# Motor_Control_-_Phase_A.net
KiCad netlist of a schematic drawn in Altium Designer
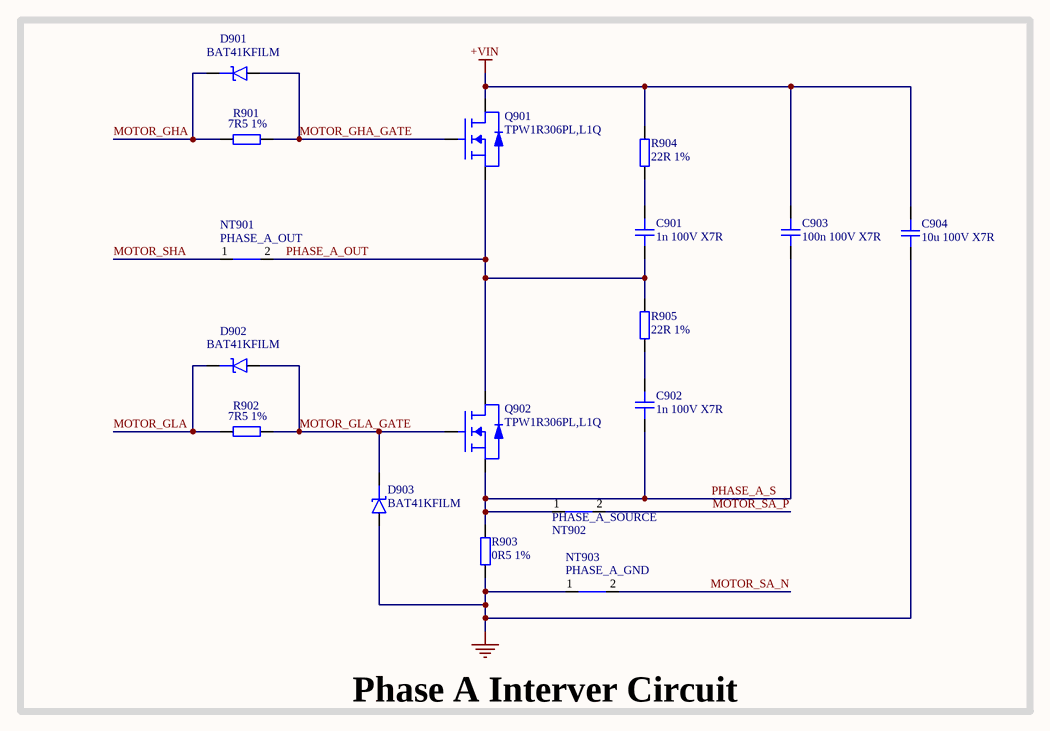
[diagram p0: Motor Control - Phase A.SchDoc]

(export (version "E")
  (design (tool "Eeschema 10.0.6"))
  (components
    (comp (ref "C901")
      (value "1n 100V X7R")
      (footprint "CAP_0805")
      (description "Capacitor SMD 0805")
      (fields
        (field (name "MANUFACTURER") "Kyocera AVX")
        (field (name "MANUFACTURER PART NUMBER") "08051C102JAT2A")
      )
      (libsource (lib "Schematic-Lib-PhilsLab") (part "CAP_0805"))
    )
    (comp (ref "C902")
      (value "1n 100V X7R")
      (footprint "CAP_0805")
      (description "Capacitor SMD 0805")
      (fields
        (field (name "MANUFACTURER") "Kyocera AVX")
        (field (name "MANUFACTURER PART NUMBER") "08051C102JAT2A")
      )
      (libsource (lib "Schematic-Lib-PhilsLab") (part "CAP_0805"))
    )
    (comp (ref "C903")
      (value "100n 100V X7R")
      (footprint "CAP_1206")
      (description "Capacitor SMD 1206")
      (fields
        (field (name "MANUFACTURER") "YAGEO")
        (field (name "MANUFACTURER PART NUMBER") "CC1206JKX7R0BB104")
      )
      (libsource (lib "Schematic-Lib-PhilsLab") (part "CAP_1206"))
    )
    (comp (ref "C904")
      (value "10u 100V X7R")
      (footprint "CAP_1210")
      (description "Capacitor SMD 1210")
      (fields
        (field (name "MANUFACTURER") "PSA(Prosperity Dielectrics)")
        (field (name "MANUFACTURER PART NUMBER") "FS32X106K101EGG")
      )
      (libsource (lib "Schematic-Lib-PhilsLab") (part "CAP_1210"))
    )
    (comp (ref "D901")
      (value "BAT41KFILM")
      (footprint "SOD-523")
      (description "Diode Schottky SMD SOD-323")
      (fields (field (name "MANUFACTURER") "STMicroelectronics"))
      (libsource (lib "Schematic-Lib-PhilsLab") (part "D_SCHOTTKY_SOD_523"))
    )
    (comp (ref "D902")
      (value "BAT41KFILM")
      (footprint "SOD-523")
      (description "Diode Schottky SMD SOD-323")
      (fields (field (name "MANUFACTURER") "STMicroelectronics"))
      (libsource (lib "Schematic-Lib-PhilsLab") (part "D_SCHOTTKY_SOD_523"))
    )
    (comp (ref "D903")
      (value "BAT41KFILM")
      (footprint "SOD-523")
      (description "Diode Schottky SMD SOD-323")
      (fields (field (name "MANUFACTURER") "STMicroelectronics"))
      (libsource (lib "Schematic-Lib-PhilsLab") (part "D_SCHOTTKY_SOD_523"))
    )
    (comp (ref "NT901")
      (value "PHASE_A_OUT")
      (footprint "NETTIE_SMD")
      (description "Net Tie SMD")
      (libsource (lib "Schematic-Lib-PhilsLab") (part "NetTie_SMD"))
    )
    (comp (ref "NT902")
      (value "PHASE_A_SOURCE")
      (footprint "NETTIE_SMD")
      (description "Net Tie SMD")
      (libsource (lib "Schematic-Lib-PhilsLab") (part "NetTie_SMD"))
    )
    (comp (ref "NT903")
      (value "PHASE_A_GND")
      (footprint "NETTIE_SMD")
      (description "Net Tie SMD")
      (libsource (lib "Schematic-Lib-PhilsLab") (part "NetTie_SMD"))
    )
    (comp (ref "Q901")
      (value "TPW1R306PL,L1Q")
      (footprint "PowerPAK-SO-8")
      (description "MOSFET N-Channel Vds=30V Id=351A Rds=470uR")
      (fields
        (field (name "MANUFACTURER") "Vishay")
        (field (name "MANUFACTURER PART NUMBER") "SIR500DP-T1-RE3")
      )
      (libsource (lib "Schematic-Lib-PhilsLab") (part "SIR500DP-T1-RE3"))
    )
    (comp (ref "Q902")
      (value "TPW1R306PL,L1Q")
      (footprint "PowerPAK-SO-8")
      (description "MOSFET N-Channel Vds=30V Id=351A Rds=470uR")
      (fields
        (field (name "MANUFACTURER") "Vishay")
        (field (name "MANUFACTURER PART NUMBER") "SIR500DP-T1-RE3")
      )
      (libsource (lib "Schematic-Lib-PhilsLab") (part "SIR500DP-T1-RE3"))
    )
    (comp (ref "R901")
      (value "7R5 1%")
      (footprint "RES_0603")
      (description "Resistor SMD 0603")
      (fields
        (field (name "MANUFACTURER") "PANASONIC")
        (field (name "MANUFACTURER PART NUMBER") "ERJPA3J7R5V")
      )
      (libsource (lib "Schematic-Lib-PhilsLab") (part "RES_0603"))
    )
    (comp (ref "R902")
      (value "7R5 1%")
      (footprint "RES_0603")
      (description "Resistor SMD 0603")
      (fields
        (field (name "MANUFACTURER") "PANASONIC")
        (field (name "MANUFACTURER PART NUMBER") "ERJPA3J7R5V")
      )
      (libsource (lib "Schematic-Lib-PhilsLab") (part "RES_0603"))
    )
    (comp (ref "R903")
      (value "0R5 1%")
      (footprint "RES_1206")
      (description "Resistor SMD 1206")
      (fields
        (field (name "MANUFACTURER") "Milliohm")
        (field (name "MANUFACTURER PART NUMBER") "HoSRX1206-3W-0.5mR-1%")
      )
      (libsource (lib "Schematic-Lib-PhilsLab") (part "RES_1206"))
    )
    (comp (ref "R904")
      (value "22R 1%")
      (footprint "RES_0805")
      (description "Resistor SMD 0805")
      (fields
        (field (name "MANUFACTURER") "Viking Tech")
        (field (name "MANUFACTURER PART NUMBER") "ARG05FTC0220")
      )
      (libsource (lib "Schematic-Lib-PhilsLab") (part "RES_0805"))
    )
    (comp (ref "R905")
      (value "22R 1%")
      (footprint "RES_0805")
      (description "Resistor SMD 0805")
      (fields
        (field (name "MANUFACTURER") "Viking Tech")
        (field (name "MANUFACTURER PART NUMBER") "ARG05FTC0220")
      )
      (libsource (lib "Schematic-Lib-PhilsLab") (part "RES_0805"))
    )
  )
  (nets
    (net (code "1") (name "+VIN") (class "Default")
      (node (ref "C903") (pin "2") (pinfunction "2_2") (pintype "passive"))
      (node (ref "C904") (pin "2") (pinfunction "2_2") (pintype "passive"))
      (node (ref "Q901") (pin "D") (pinfunction "D_D") (pintype "passive"))
      (node (ref "R904") (pin "2") (pinfunction "2_2") (pintype "passive"))
    )
    (net (code "2") (name "/MOTOR_GHA") (class "Default")
      (node (ref "D901") (pin "K") (pinfunction "K_K") (pintype "passive"))
      (node (ref "R901") (pin "1") (pinfunction "1_1") (pintype "passive"))
    )
    (net (code "3") (name "/MOTOR_GHA_GATE") (class "Default")
      (node (ref "D901") (pin "A") (pinfunction "A_A") (pintype "passive"))
      (node (ref "Q901") (pin "G") (pinfunction "G_G") (pintype "passive"))
      (node (ref "R901") (pin "2") (pinfunction "2_2") (pintype "passive"))
    )
    (net (code "4") (name "/MOTOR_GLA") (class "Default")
      (node (ref "D902") (pin "K") (pinfunction "K_K") (pintype "passive"))
      (node (ref "R902") (pin "1") (pinfunction "1_1") (pintype "passive"))
    )
    (net (code "5") (name "/MOTOR_GLA_GATE") (class "Default")
      (node (ref "D902") (pin "A") (pinfunction "A_A") (pintype "passive"))
      (node (ref "D903") (pin "K") (pinfunction "K_K") (pintype "passive"))
      (node (ref "Q902") (pin "G") (pinfunction "G_G") (pintype "passive"))
      (node (ref "R902") (pin "2") (pinfunction "2_2") (pintype "passive"))
    )
    (net (code "6") (name "/MOTOR_SA_N") (class "Default")
      (node (ref "NT903") (pin "2") (pinfunction "2_2") (pintype "passive"))
    )
    (net (code "7") (name "/MOTOR_SA_P") (class "Default")
      (node (ref "NT902") (pin "2") (pinfunction "2_2") (pintype "passive"))
    )
    (net (code "8") (name "/MOTOR_SHA") (class "Default")
      (node (ref "NT901") (pin "1") (pinfunction "1_1") (pintype "passive"))
    )
    (net (code "9") (name "/PHASE_A_OUT") (class "Default")
      (node (ref "C901") (pin "1") (pinfunction "1_1") (pintype "passive"))
      (node (ref "NT901") (pin "2") (pinfunction "2_2") (pintype "passive"))
      (node (ref "Q901") (pin "S") (pinfunction "S_S") (pintype "passive"))
      (node (ref "Q902") (pin "D") (pinfunction "D_D") (pintype "passive"))
      (node (ref "R905") (pin "2") (pinfunction "2_2") (pintype "passive"))
    )
    (net (code "10") (name "/PHASE_A_S") (class "Default")
      (node (ref "C902") (pin "1") (pinfunction "1_1") (pintype "passive"))
      (node (ref "C903") (pin "1") (pinfunction "1_1") (pintype "passive"))
      (node (ref "NT902") (pin "1") (pinfunction "1_1") (pintype "passive"))
      (node (ref "Q902") (pin "S") (pinfunction "S_S") (pintype "passive"))
      (node (ref "R903") (pin "2") (pinfunction "2_2") (pintype "passive"))
    )
    (net (code "11") (name "GND") (class "Default")
      (node (ref "C904") (pin "1") (pinfunction "1_1") (pintype "passive"))
      (node (ref "D903") (pin "A") (pinfunction "A_A") (pintype "passive"))
      (node (ref "NT903") (pin "1") (pinfunction "1_1") (pintype "passive"))
      (node (ref "R903") (pin "1") (pinfunction "1_1") (pintype "passive"))
    )
    (net (code "12") (name "Net-(C901-Pad2)") (class "Default")
      (node (ref "C901") (pin "2") (pinfunction "2_2") (pintype "passive"))
      (node (ref "R904") (pin "1") (pinfunction "1_1") (pintype "passive"))
    )
    (net (code "13") (name "Net-(C902-Pad2)") (class "Default")
      (node (ref "C902") (pin "2") (pinfunction "2_2") (pintype "passive"))
      (node (ref "R905") (pin "1") (pinfunction "1_1") (pintype "passive"))
    )
  )
)
